# US_SB_GC.net
KiCad netlist of a schematic drawn in Altium Designer
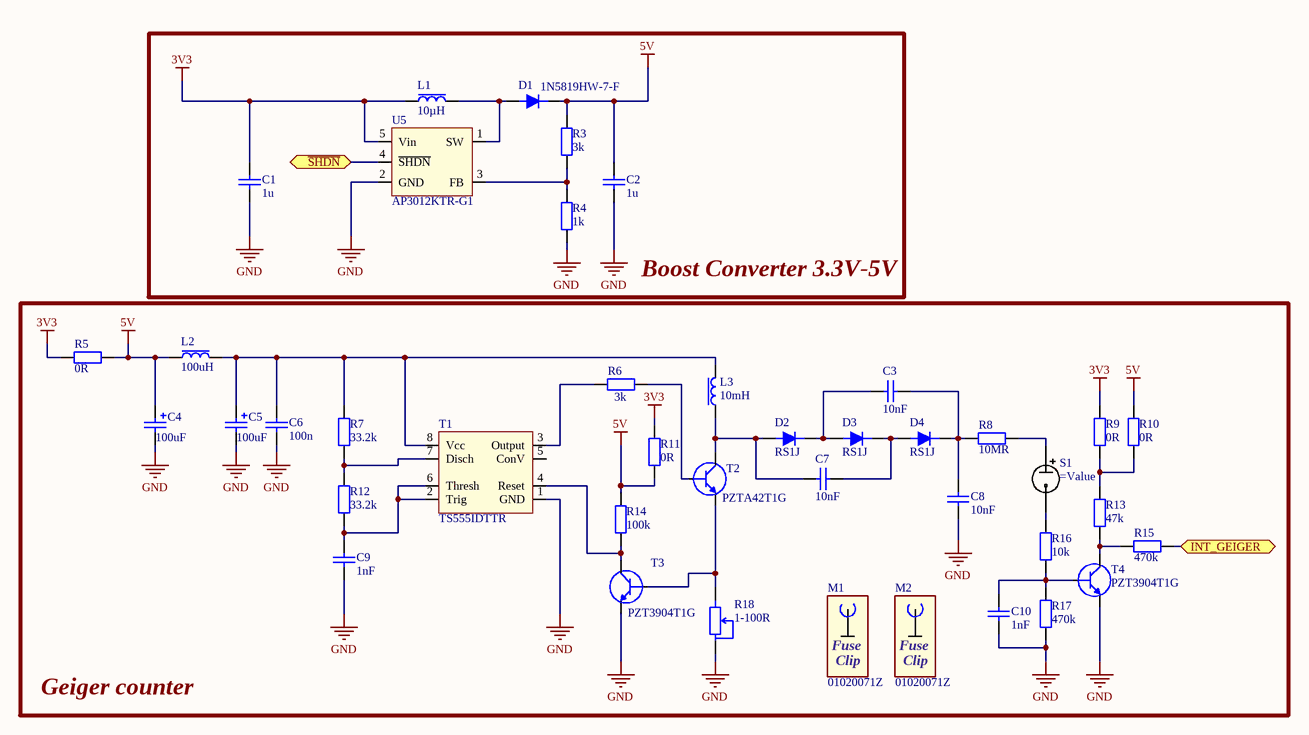
[diagram p0: US_SB_GC.SchDoc]

(export (version "E")
  (design (tool "Eeschema 10.0.6"))
  (components
    (comp (ref "C1")
      (value "1u")
      (footprint "C0603_IPC_HD")
      (description "CAP CER 1UF 16V X7R 0603")
      (fields
        (field (name "MANUFACTURER") "Samsung Electro-Mechanics")
        (field (name "MANUFACTURER PART NUMBER") "CL10B105MO8NNWC")
      )
      (libsource (lib "alfasat_lib") (part "CL10B105MO8NNWC"))
    )
    (comp (ref "C2")
      (value "1u")
      (footprint "C0603_IPC_HD")
      (description "CAP CER 1UF 16V X7R 0603")
      (fields
        (field (name "MANUFACTURER") "Samsung Electro-Mechanics")
        (field (name "MANUFACTURER PART NUMBER") "CL10B105MO8NNWC")
      )
      (libsource (lib "alfasat_lib") (part "CL10B105MO8NNWC"))
    )
    (comp (ref "C3")
      (value "10nF")
      (footprint "Chip2Pin1206_10n")
      (description "CAP CER 10000PF 1000V X7R 1206")
      (fields
        (field (name "MANUFACTURER") "Wurth Electronics Inc.")
        (field (name "MANUFACTURER PART NUMBER") "885342208021")
      )
      (libsource (lib "alfasat_lib_eps") (part "CL1206_10nF_1000V"))
    )
    (comp (ref "C4")
      (value "100uF")
      (footprint "CAPAE7866X77_100uF16V")
      (description "CAP ALUM 100UF 20% 16V SMD")
      (fields
        (field (name "MANUFACTURER") "Panasonic Electronic Components")
        (field (name "MANUFACTURER PART NUMBER") "EEE-HC1C101XP")
      )
      (libsource (lib "alfasat_lib_eps") (part "CP100uF_16V"))
    )
    (comp (ref "C5")
      (value "100uF")
      (footprint "CAPAE7866X77_100uF16V")
      (description "CAP ALUM 100UF 20% 16V SMD")
      (fields
        (field (name "MANUFACTURER") "Panasonic Electronic Components")
        (field (name "MANUFACTURER PART NUMBER") "EEE-HC1C101XP")
      )
      (libsource (lib "alfasat_lib_eps") (part "CP100uF_16V"))
    )
    (comp (ref "C6")
      (value "100n")
      (footprint "C0603_IPC_HD")
      (description "CAP CER 0.1UF 16V X7R 0603")
      (fields
        (field (name "MANUFACTURER") "Samsung Electro-Mechanics")
        (field (name "MANUFACTURER PART NUMBER") "CL10B104KO8NNNC")
      )
      (libsource (lib "alfasat_parts_lib") (part "CL10B104KO8NNNC"))
    )
    (comp (ref "C7")
      (value "10nF")
      (footprint "Chip2Pin1206_10n")
      (description "CAP CER 10000PF 1000V X7R 1206")
      (fields
        (field (name "MANUFACTURER") "Wurth Electronics Inc.")
        (field (name "MANUFACTURER PART NUMBER") "885342208021")
      )
      (libsource (lib "alfasat_lib_eps") (part "CL1206_10nF_1000V"))
    )
    (comp (ref "C8")
      (value "10nF")
      (footprint "Chip2Pin1206_10n")
      (description "CAP CER 10000PF 1000V X7R 1206")
      (fields
        (field (name "MANUFACTURER") "Wurth Electronics Inc.")
        (field (name "MANUFACTURER PART NUMBER") "885342208021")
      )
      (libsource (lib "alfasat_lib_eps") (part "CL1206_10nF_1000V"))
    )
    (comp (ref "C9")
      (value "1nF")
      (footprint "C0603_IPC_MD")
      (description "CAP CER 1000PF 50V X7R 0603")
      (fields
        (field (name "MANUFACTURER") "Samsung Electro-Mechanics")
        (field (name "MANUFACTURER PART NUMBER") "CL10B102KB8NNNC")
      )
      (libsource (lib "alfasat_lib_eps") (part "CL0603_1nF_0603"))
    )
    (comp (ref "C10")
      (value "1nF")
      (footprint "C0603_IPC_MD")
      (description "CAP CER 1000PF 50V X7R 0603")
      (fields
        (field (name "MANUFACTURER") "Samsung Electro-Mechanics")
        (field (name "MANUFACTURER PART NUMBER") "CL10B102KB8NNNC")
      )
      (libsource (lib "alfasat_lib_eps") (part "CL0603_1nF_0603"))
    )
    (comp (ref "D1")
      (value "1N5819HW-7-F")
      (footprint "1N5819HW_SODFL370X135-2N")
      (description "DIODE SCHOTTKY 40V 1A SOD123")
      (fields (field (name "MANUFACTURER") "Diodes Incorporated"))
      (libsource (lib "alfasat_lib_eps") (part "1N5819HW"))
    )
    (comp (ref "D2")
      (value "RS1J")
      (footprint "alfasat_lib_eps:RS1J-DFN")
      (description "DIODE GEN PURP 600V 1A SMA")
      (fields (field (name "MANUFACTURER") "ON Semiconductor"))
      (libsource (lib "alfasat_lib_eps") (part "RS1A-M"))
    )
    (comp (ref "D3")
      (value "RS1J")
      (footprint "alfasat_lib_eps:RS1J-DFN")
      (description "DIODE GEN PURP 600V 1A SMA")
      (fields (field (name "MANUFACTURER") "ON Semiconductor"))
      (libsource (lib "alfasat_lib_eps") (part "RS1A-M"))
    )
    (comp (ref "D4")
      (value "RS1J")
      (footprint "alfasat_lib_eps:RS1J-DFN")
      (description "DIODE GEN PURP 600V 1A SMA")
      (fields (field (name "MANUFACTURER") "ON Semiconductor"))
      (libsource (lib "alfasat_lib_eps") (part "RS1A-M"))
    )
    (comp (ref "L1")
      (value "10µH")
      (footprint "NRH3012T100MN")
      (description "10µH Shielded Wirewound Inductor 720mA 324mOhm Max Nonstandard")
      (fields
        (field (name "MANUFACTURER") "Taiyo Yuden")
        (field (name "MANUFACTURER PART NUMBER") "NRH3012T100MN")
      )
      (libsource (lib "alfasat_lib_eps") (part "10uH_Inductor_720mA"))
    )
    (comp (ref "L2")
      (value "100uH")
      (footprint "IND100uH_4040X18N")
      (description "100µH Inductor 280mA 1.74 Ohm Max Nonstandard")
      (fields
        (field (name "MANUFACTURER") "Taiyo Yuden")
        (field (name "MANUFACTURER PART NUMBER") "NRS4018T101MDGJ")
      )
      (libsource (lib "alfasat_lib_eps") (part "100UH.Inductor 280mA"))
    )
    (comp (ref "L3")
      (value "10mH")
      (footprint "IND10mH_12.7X12.7")
      (description "10mH Shielded Wirewound Inductor 180mA 19.2 Ohm Max Nonstandard")
      (fields
        (field (name "MANUFACTURER") "Bourns Inc.")
        (field (name "MANUFACTURER PART NUMBER") "SRR1208-103KL")
      )
      (libsource (lib "alfasat_lib_eps") (part "10mH Inductor 180mA"))
    )
    (comp (ref "M1")
      (value "01020071Z")
      (description "FUSE CLIP")
      (fields (field (name "MANUFACTURER") "Littelfuse Inc."))
      (libsource (lib "alfasat_lib_eps") (part "FUSE_CLIP"))
    )
    (comp (ref "M2")
      (value "01020071Z")
      (description "FUSE CLIP")
      (fields (field (name "MANUFACTURER") "Littelfuse Inc."))
      (libsource (lib "alfasat_lib_eps") (part "FUSE_CLIP"))
    )
    (comp (ref "R3")
      (value "3k")
      (footprint "C0603_IPC_HD")
      (description "RES SMD 3K OHM 5% 1/10W 0603")
      (fields
        (field (name "MANUFACTURER") "Bourns Inc.")
        (field (name "MANUFACTURER PART NUMBER") "CR0603-JW-302ELF")
      )
      (libsource (lib "alfasat_lib_eps") (part "CR0603-JW-3k"))
    )
    (comp (ref "R4")
      (value "1k")
      (footprint "R0603_IPC_MD")
      (description "RES SMD 1K OHM 5% 1/10W 0603")
      (fields
        (field (name "MANUFACTURER") "Bourns Inc.")
        (field (name "MANUFACTURER PART NUMBER") "CR0603-JW-102ELF")
      )
      (libsource (lib "alfasat_lib") (part "CR0603-JW-102ELF"))
    )
    (comp (ref "R5")
      (value "0R")
      (footprint "R0603_IPC_MD")
      (description "RES SMD 0 OHM JUMPER 1/10W 0603")
      (fields
        (field (name "MANUFACTURER") "Bourns Inc.")
        (field (name "MANUFACTURER PART NUMBER") "CR0603-J/-000ELF")
      )
      (libsource (lib "") (part "CR0603-J/-000ELF_1"))
    )
    (comp (ref "R6")
      (value "3k")
      (footprint "C0603_IPC_HD")
      (description "RES SMD 3K OHM 5% 1/10W 0603")
      (fields
        (field (name "MANUFACTURER") "Bourns Inc.")
        (field (name "MANUFACTURER PART NUMBER") "CR0603-JW-302ELF")
      )
      (libsource (lib "") (part "CR0603-JW-3k_1"))
    )
    (comp (ref "R7")
      (value "33.2k")
      (footprint "R0603_IPC_MD")
      (description "RES 33.2K OHM 1% 1/10W 0603")
      (fields
        (field (name "MANUFACTURER") "Stackpole Electronics Inc")
        (field (name "MANUFACTURER PART NUMBER") "RMCF0603FT33K2")
      )
      (libsource (lib "alfasat_lib") (part "RMCF0603FT33K2"))
    )
    (comp (ref "R8")
      (value "10MR")
      (footprint "C1206_IPC_MD")
      (description "RES SMD 10M OHM 5% 1/4W 1206")
      (fields
        (field (name "MANUFACTURER") "Bourns Inc.")
        (field (name "MANUFACTURER PART NUMBER") "CR1206-JW-106ELF")
      )
      (libsource (lib "alfasat_lib_eps") (part "CR1206-JW-10MOm"))
    )
    (comp (ref "R9")
      (value "0R")
      (footprint "R0603_IPC_MD")
      (description "RES SMD 0 OHM JUMPER 1/10W 0603")
      (fields
        (field (name "MANUFACTURER") "Bourns Inc.")
        (field (name "MANUFACTURER PART NUMBER") "CR0603-J/-000ELF")
      )
      (libsource (lib "alfasat_lib") (part "CR0603-J/-000ELF"))
    )
    (comp (ref "R10")
      (value "0R")
      (footprint "R0603_IPC_MD")
      (description "RES SMD 0 OHM JUMPER 1/10W 0603")
      (fields
        (field (name "MANUFACTURER") "Bourns Inc.")
        (field (name "MANUFACTURER PART NUMBER") "CR0603-J/-000ELF")
      )
      (libsource (lib "alfasat_lib") (part "CR0603-J/-000ELF"))
    )
    (comp (ref "R11")
      (value "0R")
      (footprint "R0603_IPC_MD")
      (description "RES SMD 0 OHM JUMPER 1/10W 0603")
      (fields
        (field (name "MANUFACTURER") "Bourns Inc.")
        (field (name "MANUFACTURER PART NUMBER") "CR0603-J/-000ELF")
      )
      (libsource (lib "alfasat_lib") (part "CR0603-J/-000ELF"))
    )
    (comp (ref "R12")
      (value "33.2k")
      (footprint "R0603_IPC_MD")
      (description "RES 33.2K OHM 1% 1/10W 0603")
      (fields
        (field (name "MANUFACTURER") "Stackpole Electronics Inc")
        (field (name "MANUFACTURER PART NUMBER") "RMCF0603FT33K2")
      )
      (libsource (lib "alfasat_lib") (part "RMCF0603FT33K2"))
    )
    (comp (ref "R13")
      (value "47k")
      (footprint "R0603_IPC_HD")
      (description "RES SMD 47K OHM 5% 1/10W 0603")
      (fields
        (field (name "MANUFACTURER") "Bourns Inc.")
        (field (name "MANUFACTURER PART NUMBER") "CR0603-JW-473ELF")
      )
      (libsource (lib "alfasat_lib_eps") (part "CR0603-JW-473ELF"))
    )
    (comp (ref "R14")
      (value "100k")
      (footprint "R0603_IPC_MD")
      (description "RES 100K OHM 1% 1/10W 0603")
      (fields
        (field (name "MANUFACTURER") "Stackpole Electronics Inc")
        (field (name "MANUFACTURER PART NUMBER") "RMCF0603FT100K")
      )
      (libsource (lib "alfasat_lib_eps") (part "CR0603-JW-104ELF"))
    )
    (comp (ref "R15")
      (value "470k")
      (footprint "C0603_IPC_HD")
      (description "RES SMD 470K OHM 5% 1/10W 0603")
      (fields
        (field (name "MANUFACTURER") "Bourns Inc.")
        (field (name "MANUFACTURER PART NUMBER") "CR0603-JW-474ELF")
      )
      (libsource (lib "") (part "CR0603-JW-470k_1"))
    )
    (comp (ref "R16")
      (value "10k")
      (footprint "C1206_IPC_HD")
      (description "RES SMD 10K OHM 5% 1/4W 1206")
      (fields
        (field (name "MANUFACTURER") "Bourns Inc.")
        (field (name "MANUFACTURER PART NUMBER") "CR1206-JW-103ELF")
      )
      (libsource (lib "alfasat_lib_eps") (part "CR1206-JW-10k"))
    )
    (comp (ref "R17")
      (value "470k")
      (footprint "C0603_IPC_HD")
      (description "RES SMD 470K OHM 5% 1/10W 0603")
      (fields
        (field (name "MANUFACTURER") "Bourns Inc.")
        (field (name "MANUFACTURER PART NUMBER") "CR0603-JW-474ELF")
      )
      (libsource (lib "alfasat_lib_eps") (part "CR0603-JW-470k"))
    )
    (comp (ref "R18")
      (value "1-100R")
      (footprint "3296W_POT")
      (description "100 ±10% ±250ppm/℃ 3296W Precision Potentiometer RoH")
      (fields
        (field (name "MANUFACTURER") "Chengdu Guosheng Tech")
        (field (name "MANUFACTURER PART NUMBER") "3296W-1-101")
      )
      (libsource (lib "alfasat_lib_eps") (part "3296W-1-101R"))
    )
    (comp (ref "S1")
      (value "~")
      (footprint "SI-3BG")
      (description "FUSE CLIP CARTRIDGE PCB (FOR GEIGER TUBE)")
      (fields (field (name "MANUFACTURER") "USSR") (field (name "MANUFACTURER PART NUMBER") "SI-3BG"))
      (libsource (lib "alfasat_lib_eps") (part "GEIGER TUBE"))
    )
    (comp (ref "T1")
      (value "TS555IDTTR")
      (footprint "SOIC127P600X175-(TS555)")
      (description "555 Type, Timer/Oscillator (Single) IC 2.7MHz 8-SO")
      (fields (field (name "MANUFACTURER") "STMicroelectronics"))
      (libsource (lib "alfasat_lib_eps") (part "TS555"))
    )
    (comp (ref "T2")
      (value "PZTA42T1G")
      (footprint "alfasat_lib_eps:PZTA42T1G_SOT230P")
      (description "Bipolar (BJT) Transistor NPN 300V 500mA 50MHz 1.5W Surface Mount SOT-223")
      (fields (field (name "MANUFACTURER") "ON Semiconductor"))
      (libsource (lib "alfasat_lib_eps") (part "PZTA42T1(MPSA42 )"))
    )
    (comp (ref "T3")
      (value "PZT3904T1G")
      (footprint "alfasat_lib_eps:PZT3904_SOT223")
      (description "Bipolar (BJT) Transistor NPN 40V 200mA 300MHz 1.5W Surface Mount SOT-223")
      (fields (field (name "MANUFACTURER") "ON Semiconductor"))
      (libsource (lib "alfasat_lib_eps") (part "PZT3904(2N3904)"))
    )
    (comp (ref "T4")
      (value "PZT3904T1G")
      (footprint "alfasat_lib_eps:PZT3904_SOT223")
      (description "Bipolar (BJT) Transistor NPN 40V 200mA 300MHz 1.5W Surface Mount SOT-223")
      (fields (field (name "MANUFACTURER") "ON Semiconductor"))
      (libsource (lib "alfasat_lib_eps") (part "PZT3904(2N3904)"))
    )
    (comp (ref "U5")
      (value "AP3012KTR-G1")
      (footprint "AP3012_SOT95P280X145-5N")
      (description "Boost Switching Regulator IC Positive Adjustable 1.25V 1 Output 500mA (Switch) SC-74A, SOT-753")
      (fields (field (name "MANUFACTURER") "Diodes Incorporated"))
      (libsource (lib "alfasat_lib_eps") (part "AP3012KTR"))
    )
  )
  (nets
    (net (code "1") (name "/INT_GEIGER") (class "Default")
      (node (ref "R15") (pin "2") (pinfunction "2_2") (pintype "passive"))
    )
    (net (code "2") (name "/~{SHDN}") (class "Default")
      (node (ref "U5") (pin "4") (pinfunction "~{SHDN}_4") (pintype "passive"))
    )
    (net (code "3") (name "3V3") (class "Default")
      (node (ref "C1") (pin "2") (pinfunction "2_2") (pintype "passive"))
      (node (ref "L1") (pin "1") (pinfunction "1_1") (pintype "passive"))
      (node (ref "R11") (pin "2") (pinfunction "2_2") (pintype "passive"))
      (node (ref "R5") (pin "1") (pinfunction "1_1") (pintype "passive"))
      (node (ref "R9") (pin "2") (pinfunction "2_2") (pintype "passive"))
      (node (ref "U5") (pin "5") (pinfunction "Vin_5") (pintype "passive"))
    )
    (net (code "4") (name "5V") (class "Default")
      (node (ref "C2") (pin "2") (pinfunction "2_2") (pintype "passive"))
      (node (ref "C4") (pin "1") (pinfunction "1_1") (pintype "passive"))
      (node (ref "D1") (pin "2") (pinfunction "2_2") (pintype "passive"))
      (node (ref "L2") (pin "1") (pinfunction "1_1") (pintype "passive"))
      (node (ref "R10") (pin "2") (pinfunction "2_2") (pintype "passive"))
      (node (ref "R11") (pin "1") (pinfunction "1_1") (pintype "passive"))
      (node (ref "R14") (pin "2") (pinfunction "2_2") (pintype "passive"))
      (node (ref "R3") (pin "2") (pinfunction "2_2") (pintype "passive"))
      (node (ref "R5") (pin "2") (pinfunction "2_2") (pintype "passive"))
    )
    (net (code "5") (name "GND") (class "Default")
      (node (ref "C1") (pin "1") (pinfunction "1_1") (pintype "passive"))
      (node (ref "C10") (pin "1") (pinfunction "1_1") (pintype "passive"))
      (node (ref "C2") (pin "1") (pinfunction "1_1") (pintype "passive"))
      (node (ref "C4") (pin "2") (pinfunction "2_2") (pintype "passive"))
      (node (ref "C5") (pin "2") (pinfunction "2_2") (pintype "passive"))
      (node (ref "C6") (pin "2") (pinfunction "2_2") (pintype "passive"))
      (node (ref "C8") (pin "1") (pinfunction "1_1") (pintype "passive"))
      (node (ref "C9") (pin "1") (pinfunction "1_1") (pintype "passive"))
      (node (ref "R17") (pin "1") (pinfunction "1_1") (pintype "passive"))
      (node (ref "R18") (pin "2") (pinfunction "2_2") (pintype "passive"))
      (node (ref "R4") (pin "1") (pinfunction "1_1") (pintype "passive"))
      (node (ref "T1") (pin "1") (pinfunction "GND_1") (pintype "passive"))
      (node (ref "T3") (pin "3") (pinfunction "E_3") (pintype "passive"))
      (node (ref "T4") (pin "3") (pinfunction "E_3") (pintype "passive"))
      (node (ref "U5") (pin "2") (pinfunction "GND_2") (pintype "passive"))
    )
    (net (code "6") (name "Net-(C3-Pad1)") (class "Default")
      (node (ref "C3") (pin "1") (pinfunction "1_1") (pintype "passive"))
      (node (ref "D2") (pin "2") (pinfunction "2_2") (pintype "passive"))
      (node (ref "D3") (pin "1") (pinfunction "1_1") (pintype "passive"))
    )
    (net (code "7") (name "Net-(C3-Pad2)") (class "Default")
      (node (ref "C3") (pin "2") (pinfunction "2_2") (pintype "passive"))
      (node (ref "C8") (pin "2") (pinfunction "2_2") (pintype "passive"))
      (node (ref "D4") (pin "2") (pinfunction "2_2") (pintype "passive"))
      (node (ref "R8") (pin "1") (pinfunction "1_1") (pintype "passive"))
    )
    (net (code "8") (name "Net-(C7-Pad2)") (class "Default")
      (node (ref "C7") (pin "2") (pinfunction "2_2") (pintype "passive"))
      (node (ref "D3") (pin "2") (pinfunction "2_2") (pintype "passive"))
      (node (ref "D4") (pin "1") (pinfunction "1_1") (pintype "passive"))
    )
    (net (code "9") (name "Net-(R8-Pad2)") (class "Default")
      (node (ref "R8") (pin "2") (pinfunction "2_2") (pintype "passive"))
      (node (ref "S1") (pin "1") (pinfunction "1_1") (pintype "passive"))
    )
    (net (code "10") (name "Net-(R10-Pad1)") (class "Default")
      (node (ref "R10") (pin "1") (pinfunction "1_1") (pintype "passive"))
      (node (ref "R13") (pin "2") (pinfunction "2_2") (pintype "passive"))
      (node (ref "R9") (pin "1") (pinfunction "1_1") (pintype "passive"))
    )
    (net (code "11") (name "Net-(R16-Pad2)") (class "Default")
      (node (ref "R16") (pin "2") (pinfunction "2_2") (pintype "passive"))
      (node (ref "S1") (pin "2") (pinfunction "2_2") (pintype "passive"))
    )
    (net (code "12") (name "Net-(T1-Disch)") (class "Default")
      (node (ref "R12") (pin "2") (pinfunction "2_2") (pintype "passive"))
      (node (ref "R7") (pin "1") (pinfunction "1_1") (pintype "passive"))
      (node (ref "T1") (pin "7") (pinfunction "Disch_7") (pintype "passive"))
    )
    (net (code "13") (name "Net-(T1-Output)") (class "Default")
      (node (ref "R6") (pin "1") (pinfunction "1_1") (pintype "passive"))
      (node (ref "T1") (pin "3") (pinfunction "Output_3") (pintype "passive"))
    )
    (net (code "14") (name "Net-(T1-Reset)") (class "Default")
      (node (ref "R14") (pin "1") (pinfunction "1_1") (pintype "passive"))
      (node (ref "T1") (pin "4") (pinfunction "Reset_4") (pintype "passive"))
      (node (ref "T3") (pin "2") (pinfunction "C_2") (pintype "passive"))
    )
    (net (code "15") (name "Net-(T1-Thresh)") (class "Default")
      (node (ref "C9") (pin "2") (pinfunction "2_2") (pintype "passive"))
      (node (ref "R12") (pin "1") (pinfunction "1_1") (pintype "passive"))
      (node (ref "T1") (pin "2") (pinfunction "Trig_2") (pintype "passive"))
      (node (ref "T1") (pin "6") (pinfunction "Thresh_6") (pintype "passive"))
    )
    (net (code "16") (name "Net-(T1-Vcc)") (class "Default")
      (node (ref "C5") (pin "1") (pinfunction "1_1") (pintype "passive"))
      (node (ref "C6") (pin "1") (pinfunction "1_1") (pintype "passive"))
      (node (ref "L2") (pin "2") (pinfunction "2_2") (pintype "passive"))
      (node (ref "L3") (pin "2") (pinfunction "2_2") (pintype "passive"))
      (node (ref "R7") (pin "2") (pinfunction "2_2") (pintype "passive"))
      (node (ref "T1") (pin "8") (pinfunction "Vcc_8") (pintype "passive"))
    )
    (net (code "17") (name "Net-(T2-B)") (class "Default")
      (node (ref "R6") (pin "2") (pinfunction "2_2") (pintype "passive"))
      (node (ref "T2") (pin "1") (pinfunction "B_1") (pintype "passive"))
    )
    (net (code "18") (name "Net-(T2-C)") (class "Default")
      (node (ref "C7") (pin "1") (pinfunction "1_1") (pintype "passive"))
      (node (ref "D2") (pin "1") (pinfunction "1_1") (pintype "passive"))
      (node (ref "L3") (pin "1") (pinfunction "1_1") (pintype "passive"))
      (node (ref "T2") (pin "2") (pinfunction "C_2") (pintype "passive"))
    )
    (net (code "19") (name "Net-(T2-E)") (class "Default")
      (node (ref "R18") (pin "1") (pinfunction "1_1") (pintype "passive"))
      (node (ref "T2") (pin "3") (pinfunction "E_3") (pintype "passive"))
      (node (ref "T3") (pin "1") (pinfunction "B_1") (pintype "passive"))
    )
    (net (code "20") (name "Net-(T4-B)") (class "Default")
      (node (ref "C10") (pin "2") (pinfunction "2_2") (pintype "passive"))
      (node (ref "R16") (pin "1") (pinfunction "1_1") (pintype "passive"))
      (node (ref "R17") (pin "2") (pinfunction "2_2") (pintype "passive"))
      (node (ref "T4") (pin "1") (pinfunction "B_1") (pintype "passive"))
    )
    (net (code "21") (name "Net-(T4-C)") (class "Default")
      (node (ref "R13") (pin "1") (pinfunction "1_1") (pintype "passive"))
      (node (ref "R15") (pin "1") (pinfunction "1_1") (pintype "passive"))
      (node (ref "T4") (pin "2") (pinfunction "C_2") (pintype "passive"))
    )
    (net (code "22") (name "Net-(U5-FB)") (class "Default")
      (node (ref "R3") (pin "1") (pinfunction "1_1") (pintype "passive"))
      (node (ref "R4") (pin "2") (pinfunction "2_2") (pintype "passive"))
      (node (ref "U5") (pin "3") (pinfunction "FB_3") (pintype "passive"))
    )
    (net (code "23") (name "Net-(U5-SW)") (class "Default")
      (node (ref "D1") (pin "1") (pinfunction "1_1") (pintype "passive"))
      (node (ref "L1") (pin "2") (pinfunction "2_2") (pintype "passive"))
      (node (ref "U5") (pin "1") (pinfunction "SW_1") (pintype "passive"))
    )
    (net (code "24") (name "unconnected-(T1-ConV-Pad5)") (class "Default")
      (node (ref "T1") (pin "5") (pinfunction "ConV_5") (pintype "passive"))
    )
  )
)
